# CPU_MISC.net
KiCad netlist of a schematic drawn in Altium Designer
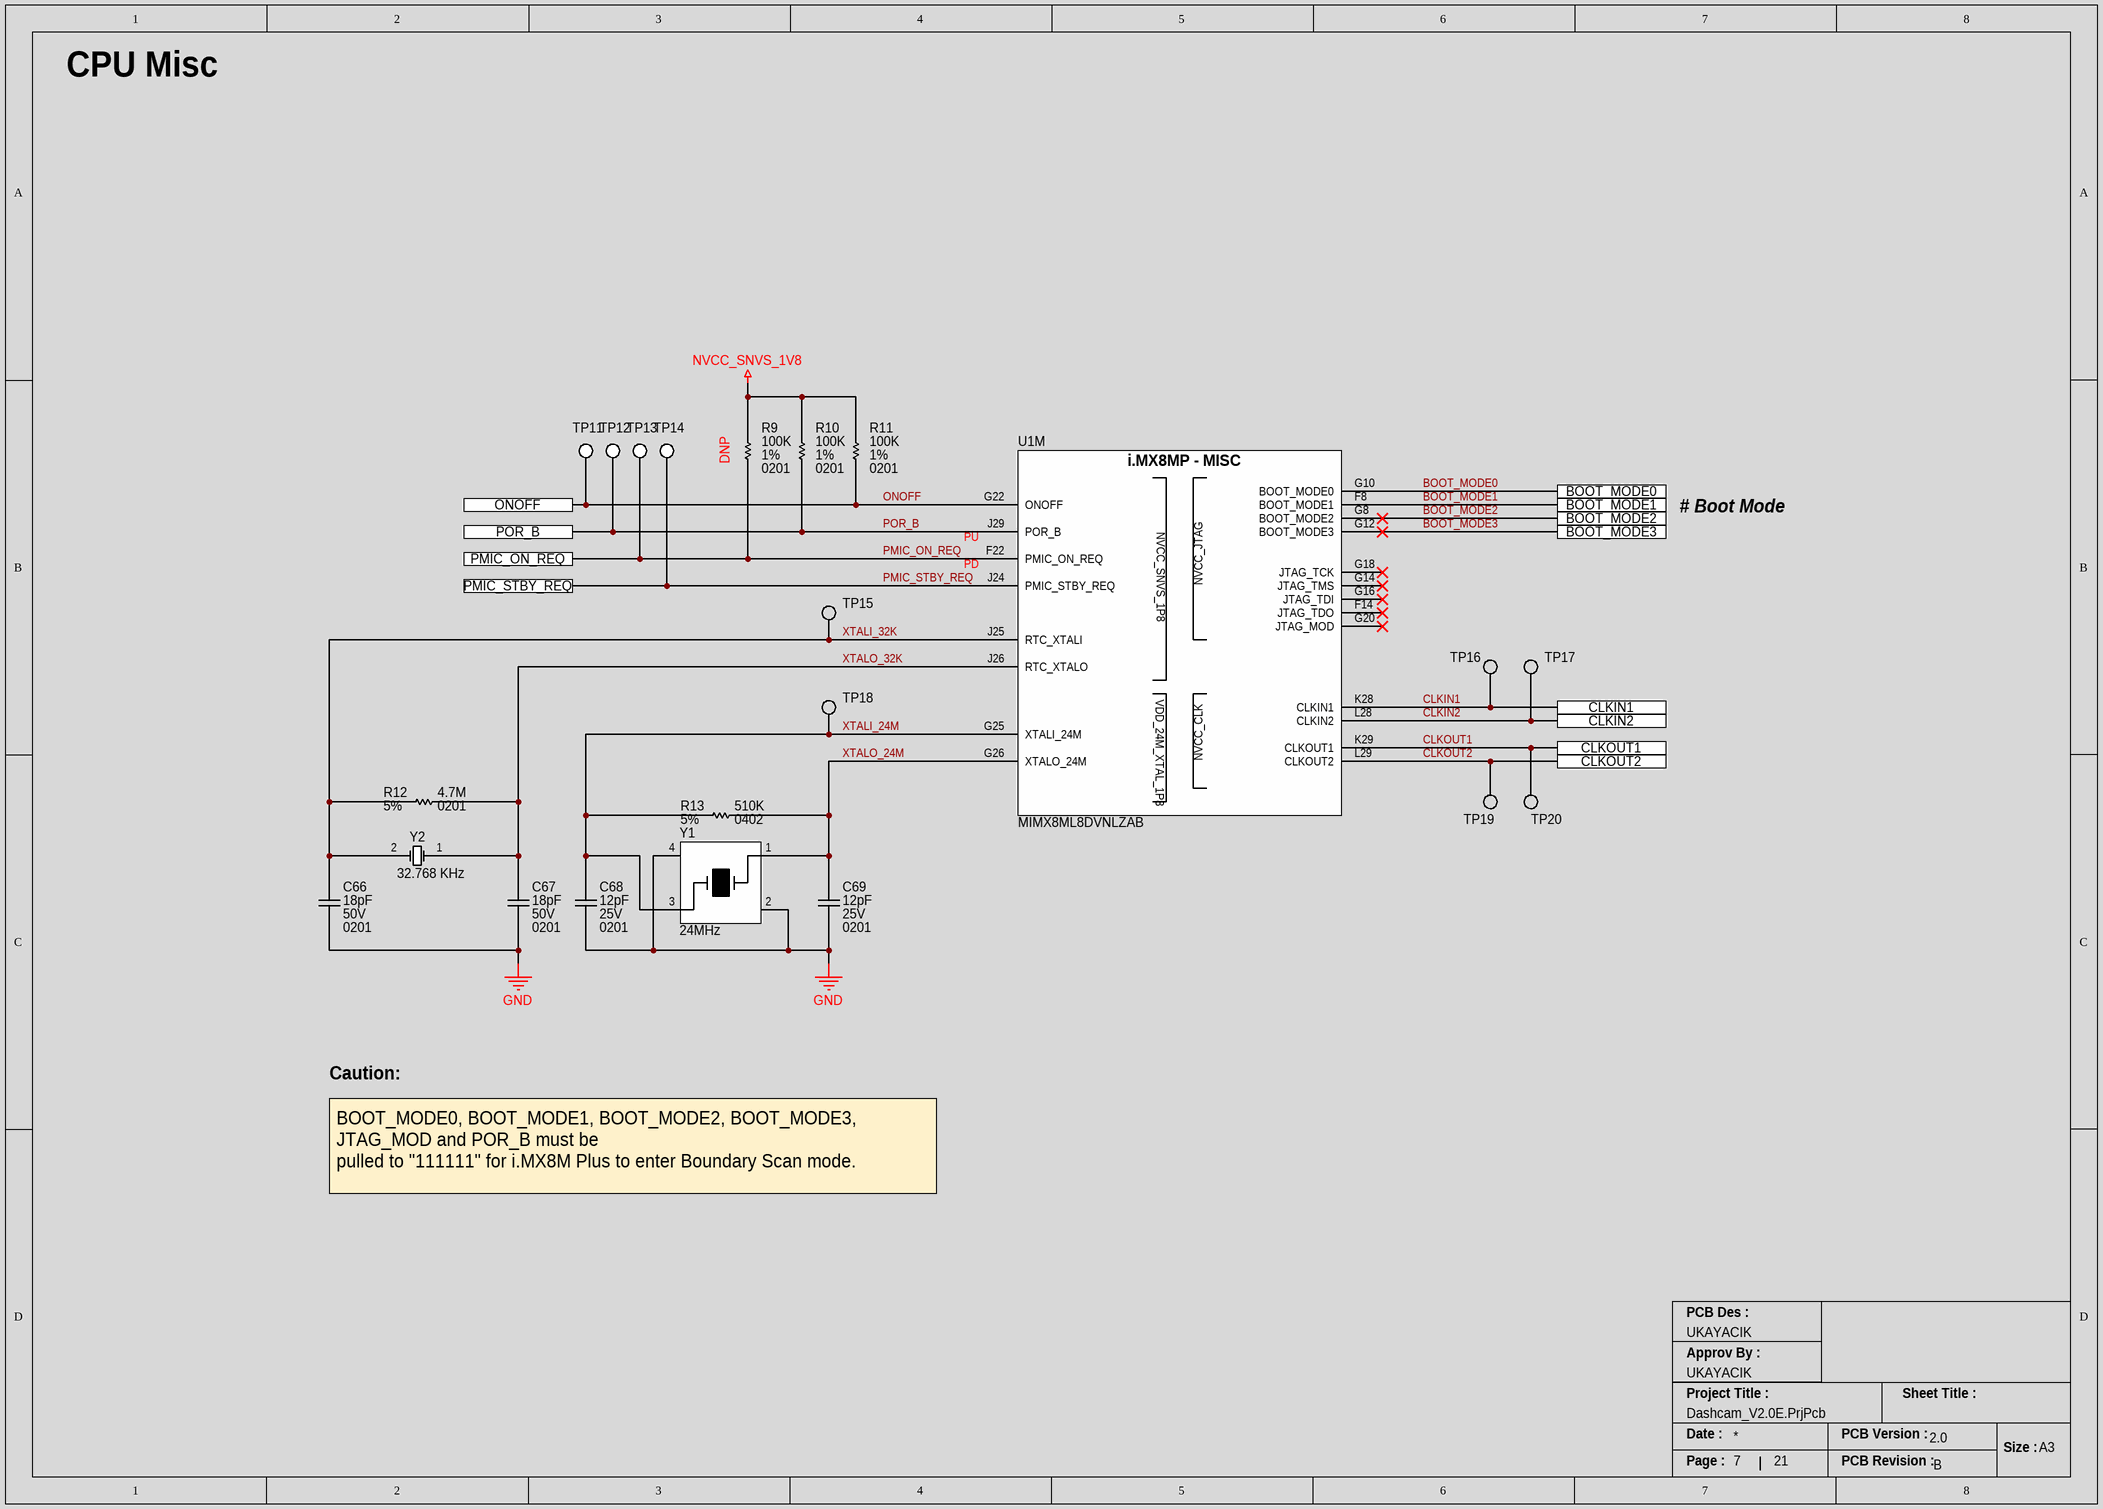
[diagram p0: CPU MISC.SchDoc]

(export (version "E")
  (design (tool "Eeschema 10.0.6"))
  (components
    (comp (ref "C66")
      (value "GRM0335C1H180JA01D")
      (footprint "CAP_0201_CAPC0603X03N")
      (description "Multilayer Ceramic Capacitor, 18 pF, 50 V, ± 5%, C0G (NP0), 0201 [0603 Metric]")
      (fields
        (field (name "MANUFACTURER") "Murata")
        (field (name "TOLERANCE") "5%")
        (field (name "CAPACITANCE") "18pF")
        (field (name "VOLTAGE RATING") "50V")
        (field (name "CASE/PACKAGE") "0201")
      )
      (libsource (lib "Electronic Devices_LIB") (part "CAP_18PF_50V_NP0_0201"))
    )
    (comp (ref "C67")
      (value "GRM0335C1H180JA01D")
      (footprint "CAP_0201_CAPC0603X03N")
      (description "Multilayer Ceramic Capacitor, 18 pF, 50 V, ± 5%, C0G (NP0), 0201 [0603 Metric]")
      (fields
        (field (name "MANUFACTURER") "Murata")
        (field (name "TOLERANCE") "5%")
        (field (name "CAPACITANCE") "18pF")
        (field (name "VOLTAGE RATING") "50V")
        (field (name "CASE/PACKAGE") "0201")
      )
      (libsource (lib "Electronic Devices_LIB") (part "CAP_18PF_50V_NP0_0201"))
    )
    (comp (ref "C68")
      (value "CGA1A2C0G1E120J030BA")
      (footprint "CAP_0201_CAPC0603X03N")
      (description "CAPACITORS CERAMIC, 12PF, 5%, 25V, C0G, 0201[0603]; Product Range: TDK - CGA Seri")
      (fields
        (field (name "MANUFACTURER") "TDK")
        (field (name "TOLERANCE") "5%")
        (field (name "VOLTAGE RATING") "25V")
        (field (name "CAPACITANCE") "12pF")
        (field (name "CASE/PACKAGE") "0201")
      )
      (libsource (lib "Electronic Devices_LIB") (part "CAP_12PF_25V_NP0_0201"))
    )
    (comp (ref "C69")
      (value "CGA1A2C0G1E120J030BA")
      (footprint "CAP_0201_CAPC0603X03N")
      (description "CAPACITORS CERAMIC, 12PF, 5%, 25V, C0G, 0201[0603]; Product Range: TDK - CGA Seri")
      (fields
        (field (name "MANUFACTURER") "TDK")
        (field (name "TOLERANCE") "5%")
        (field (name "VOLTAGE RATING") "25V")
        (field (name "CAPACITANCE") "12pF")
        (field (name "CASE/PACKAGE") "0201")
      )
      (libsource (lib "Electronic Devices_LIB") (part "CAP_12PF_25V_NP0_0201"))
    )
    (comp (ref "R9")
      (value "RC0201FR-07100KL")
      (footprint "RES_0201_RESC0603X02N")
      (description "SMD Chip Resistor, 100 kOhm, ± 1%, 50 mW, 0201 [0603 Metric], Thick Film, General Purpose")
      (fields
        (field (name "MANUFACTURER") "Yageo")
        (field (name "RESISTANCE") "100K")
        (field (name "TOLERANCE") "1%")
        (field (name "CASE/PACKAGE") "0201")
      )
      (libsource (lib "Electronic Devices_LIB") (part "RES_100K_1%_50mW_0201"))
    )
    (comp (ref "R10")
      (value "RC0201FR-07100KL")
      (footprint "RES_0201_RESC0603X02N")
      (description "SMD Chip Resistor, 100 kOhm, ± 1%, 50 mW, 0201 [0603 Metric], Thick Film, General Purpose")
      (fields
        (field (name "MANUFACTURER") "Yageo")
        (field (name "RESISTANCE") "100K")
        (field (name "TOLERANCE") "1%")
        (field (name "CASE/PACKAGE") "0201")
      )
      (libsource (lib "Electronic Devices_LIB") (part "RES_100K_1%_50mW_0201"))
    )
    (comp (ref "R11")
      (value "RC0201FR-07100KL")
      (footprint "RES_0201_RESC0603X02N")
      (description "SMD Chip Resistor, 100 kOhm, ± 1%, 50 mW, 0201 [0603 Metric], Thick Film, General Purpose")
      (fields
        (field (name "MANUFACTURER") "Yageo")
        (field (name "RESISTANCE") "100K")
        (field (name "TOLERANCE") "1%")
        (field (name "CASE/PACKAGE") "0201")
      )
      (libsource (lib "Electronic Devices_LIB") (part "RES_100K_1%_50mW_0201"))
    )
    (comp (ref "R12")
      (value "RC0201JR-074M7L")
      (footprint "RES_0201_RESC0603X02N")
      (description "SMD Chip Resistor, 4.7 MOhm, ± 5%, 50 mW, 0201 [0603 Metric], Thick Film, General Purpose")
      (fields
        (field (name "MANUFACTURER") "Yageo")
        (field (name "TOLERANCE") "5%")
        (field (name "RESISTANCE") "4.7M")
        (field (name "CASE/PACKAGE") "0201")
      )
      (libsource (lib "Electronic Devices_LIB") (part "RES_4.7M_5%_50mW_0201"))
    )
    (comp (ref "R13")
      (value "ERJ-2GEJ514X")
      (footprint "RES_0402_RESC1005X04N")
      (description "SMD Chip Resistor, 510 kOhm, ± 5%, 100 mW, 0402 [1005 Metric], Thick Film, General Purpose")
      (fields
        (field (name "MANUFACTURER") "Panasonic")
        (field (name "TOLERANCE") "5%")
        (field (name "RESISTANCE") "510K")
        (field (name "CASE/PACKAGE") "0402")
      )
      (libsource (lib "Electronic Devices_LIB") (part "RES_510K_5%_100mW_0402"))
    )
    (comp (ref "TP11")
      (value "NO COMPONENT")
      (footprint "TP_PAD_0.8MM_SMD_ROUND")
      (description "Test Point, SMD pad, round, 1.5mm, 1.6mm, 3mm diameter")
      (libsource (lib "Electronic Devices_LIB") (part "TP_PAD_SMD_Round"))
    )
    (comp (ref "TP12")
      (value "NO COMPONENT")
      (footprint "TP_PAD_0.8MM_SMD_ROUND")
      (description "Test Point, SMD pad, round, 1.5mm, 1.6mm, 3mm diameter")
      (libsource (lib "Electronic Devices_LIB") (part "TP_PAD_SMD_Round"))
    )
    (comp (ref "TP13")
      (value "NO COMPONENT")
      (footprint "TP_PAD_0.8MM_SMD_ROUND")
      (description "Test Point, SMD pad, round, 1.5mm, 1.6mm, 3mm diameter")
      (libsource (lib "Electronic Devices_LIB") (part "TP_PAD_SMD_Round"))
    )
    (comp (ref "TP14")
      (value "NO COMPONENT")
      (footprint "TP_PAD_0.8MM_SMD_ROUND")
      (description "Test Point, SMD pad, round, 1.5mm, 1.6mm, 3mm diameter")
      (libsource (lib "Electronic Devices_LIB") (part "TP_PAD_SMD_Round"))
    )
    (comp (ref "TP15")
      (value "NO COMPONENT")
      (footprint "TP_PAD_0.5MM_SMD_ROUND")
      (description "Test Point, SMD pad, round, 1.5mm, 1.6mm, 3mm diameter")
      (libsource (lib "Electronic Devices_LIB") (part "TP_PAD_SMD_SMALL"))
    )
    (comp (ref "TP16")
      (value "NO COMPONENT")
      (footprint "TP_PAD_0.5MM_SMD_ROUND")
      (description "Test Point, SMD pad, round, 1.5mm, 1.6mm, 3mm diameter")
      (libsource (lib "Electronic Devices_LIB") (part "TP_PAD_SMD_SMALL"))
    )
    (comp (ref "TP17")
      (value "NO COMPONENT")
      (footprint "TP_PAD_0.5MM_SMD_ROUND")
      (description "Test Point, SMD pad, round, 1.5mm, 1.6mm, 3mm diameter")
      (libsource (lib "Electronic Devices_LIB") (part "TP_PAD_SMD_SMALL"))
    )
    (comp (ref "TP18")
      (value "NO COMPONENT")
      (footprint "TP_PAD_0.5MM_SMD_ROUND")
      (description "Test Point, SMD pad, round, 1.5mm, 1.6mm, 3mm diameter")
      (libsource (lib "Electronic Devices_LIB") (part "TP_PAD_SMD_SMALL"))
    )
    (comp (ref "TP19")
      (value "NO COMPONENT")
      (footprint "TP_PAD_0.5MM_SMD_ROUND")
      (description "Test Point, SMD pad, round, 1.5mm, 1.6mm, 3mm diameter")
      (libsource (lib "Electronic Devices_LIB") (part "TP_PAD_SMD_SMALL"))
    )
    (comp (ref "TP20")
      (value "NO COMPONENT")
      (footprint "TP_PAD_0.5MM_SMD_ROUND")
      (description "Test Point, SMD pad, round, 1.5mm, 1.6mm, 3mm diameter")
      (libsource (lib "Electronic Devices_LIB") (part "TP_PAD_SMD_SMALL"))
    )
    (comp (ref "U1")
      (value "MIMX8ML8DVNLZAB")
      (footprint "IC_MPU_BGA548C50P29X29_1500X1500X148")
      (description "i.MX 8M Plus, Consumer, / TRAY TRAY MULTIPLE DP BAKEABLE RoHS Compliant: Yes")
      (fields (field (name "MANUFACTURER") "NXP Semiconductors"))
      (libsource (lib "Electronic Devices_LIB") (part "IC_MPU_8M_PLUS_MIMX8ML8DVNLZAB"))
    )
    (comp (ref "Y1")
      (value "TSX-3225 24.0000MF15X-AC3")
      (footprint "CRYSTAL_24MHz_OSCCC320X250X60")
      (description "24 MHz ±10ppm Crystal 9pF 40 Ohms 4-SMD, No Lead")
      (fields (field (name "MANUFACTURER") "Epson") (field (name "FREQUENCY") "24MHz"))
      (libsource (lib "Electronic Devices_LIB") (part "CRYSTAL_EPSON_24MHz_TSX-3225 24.0000MF15X-AC3"))
    )
    (comp (ref "Y2")
      (value "ABS07-32.768KHZ-T")
      (footprint "CRYSTAL_ABS07-32.768KHZ-T")
      (description "Crystal 0.032768MHz ±20ppm (Tol) 12.5pF Flexural 70000Ohm 2-Pin CSMD T/R")
      (fields
        (field (name "MANUFACTURER") "Abracon")
        (field (name "TOLERANCE") "20ppm")
        (field (name "OPERATING FREQUENCY") "32.768 KHz")
      )
      (libsource (lib "Electronic Devices_LIB") (part "CRYSTAL_ABRACON_32.768KHz_ABS07-32.768KHZ-T"))
    )
  )
  (nets
    (net (code "1") (name "/BOOT_MODE0") (class "Default")
      (node (ref "U1") (pin "G10") (pinfunction "BOOT_MODE0_G10") (pintype "passive"))
    )
    (net (code "2") (name "/BOOT_MODE1") (class "Default")
      (node (ref "U1") (pin "F8") (pinfunction "BOOT_MODE1_F8") (pintype "passive"))
    )
    (net (code "3") (name "/BOOT_MODE2") (class "Default")
      (node (ref "U1") (pin "G8") (pinfunction "BOOT_MODE2_G8") (pintype "passive+no_connect"))
    )
    (net (code "4") (name "/BOOT_MODE3") (class "Default")
      (node (ref "U1") (pin "G12") (pinfunction "BOOT_MODE3_G12") (pintype "passive+no_connect"))
    )
    (net (code "5") (name "/CLKIN1") (class "Default")
      (node (ref "TP16") (pin "1") (pinfunction "1_1") (pintype "passive"))
      (node (ref "U1") (pin "K28") (pinfunction "CLKIN1_K28") (pintype "passive"))
    )
    (net (code "6") (name "/CLKIN2") (class "Default")
      (node (ref "TP17") (pin "1") (pinfunction "1_1") (pintype "passive"))
      (node (ref "U1") (pin "L28") (pinfunction "CLKIN2_L28") (pintype "passive"))
    )
    (net (code "7") (name "/CLKOUT1") (class "Default")
      (node (ref "TP20") (pin "1") (pinfunction "1_1") (pintype "passive"))
      (node (ref "U1") (pin "K29") (pinfunction "CLKOUT1_K29") (pintype "passive"))
    )
    (net (code "8") (name "/CLKOUT2") (class "Default")
      (node (ref "TP19") (pin "1") (pinfunction "1_1") (pintype "passive"))
      (node (ref "U1") (pin "L29") (pinfunction "CLKOUT2_L29") (pintype "passive"))
    )
    (net (code "9") (name "/ONOFF") (class "Default")
      (node (ref "R11") (pin "1") (pinfunction "1_1") (pintype "passive"))
      (node (ref "TP11") (pin "1") (pinfunction "1_1") (pintype "passive"))
      (node (ref "U1") (pin "G22") (pinfunction "ONOFF_G22") (pintype "passive"))
    )
    (net (code "10") (name "/PMIC_ON_REQ") (class "Default")
      (node (ref "R9") (pin "1") (pinfunction "1_1") (pintype "passive"))
      (node (ref "TP13") (pin "1") (pinfunction "1_1") (pintype "passive"))
      (node (ref "U1") (pin "F22") (pinfunction "PMIC_ON_REQ_F22") (pintype "passive"))
    )
    (net (code "11") (name "/PMIC_STBY_REQ") (class "Default")
      (node (ref "TP14") (pin "1") (pinfunction "1_1") (pintype "passive"))
      (node (ref "U1") (pin "J24") (pinfunction "PMIC_STBY_REQ_J24") (pintype "passive"))
    )
    (net (code "12") (name "/POR_B") (class "Default")
      (node (ref "R10") (pin "1") (pinfunction "1_1") (pintype "passive"))
      (node (ref "TP12") (pin "1") (pinfunction "1_1") (pintype "passive"))
      (node (ref "U1") (pin "J29") (pinfunction "POR_B_J29") (pintype "passive"))
    )
    (net (code "13") (name "/XTALI_24M") (class "Default")
      (node (ref "C68") (pin "2") (pinfunction "2_2") (pintype "passive"))
      (node (ref "R13") (pin "1") (pinfunction "1_1") (pintype "passive"))
      (node (ref "TP18") (pin "1") (pinfunction "1_1") (pintype "passive"))
      (node (ref "U1") (pin "G25") (pinfunction "XTALI_24M_G25") (pintype "passive"))
      (node (ref "Y1") (pin "3") (pinfunction "3_3") (pintype "passive"))
    )
    (net (code "14") (name "/XTALI_32K") (class "Default")
      (node (ref "C66") (pin "2") (pinfunction "2_2") (pintype "passive"))
      (node (ref "R12") (pin "1") (pinfunction "1_1") (pintype "passive"))
      (node (ref "TP15") (pin "1") (pinfunction "1_1") (pintype "passive"))
      (node (ref "U1") (pin "J25") (pinfunction "RTC_XTALI_J25") (pintype "passive"))
      (node (ref "Y2") (pin "2") (pinfunction "OSC2_2") (pintype "passive"))
    )
    (net (code "15") (name "/XTALO_24M") (class "Default")
      (node (ref "C69") (pin "2") (pinfunction "2_2") (pintype "passive"))
      (node (ref "R13") (pin "2") (pinfunction "2_2") (pintype "passive"))
      (node (ref "U1") (pin "G26") (pinfunction "XTALO_24M_G26") (pintype "passive"))
      (node (ref "Y1") (pin "1") (pinfunction "1_1") (pintype "passive"))
    )
    (net (code "16") (name "/XTALO_32K") (class "Default")
      (node (ref "C67") (pin "2") (pinfunction "2_2") (pintype "passive"))
      (node (ref "R12") (pin "2") (pinfunction "2_2") (pintype "passive"))
      (node (ref "U1") (pin "J26") (pinfunction "RTC_XTALO_J26") (pintype "passive"))
      (node (ref "Y2") (pin "1") (pinfunction "OSC1_1") (pintype "passive"))
    )
    (net (code "17") (name "GND") (class "Default")
      (node (ref "C66") (pin "1") (pinfunction "1_1") (pintype "passive"))
      (node (ref "C67") (pin "1") (pinfunction "1_1") (pintype "passive"))
      (node (ref "C68") (pin "1") (pinfunction "1_1") (pintype "passive"))
      (node (ref "C69") (pin "1") (pinfunction "1_1") (pintype "passive"))
      (node (ref "Y1") (pin "2") (pinfunction "2_2") (pintype "passive"))
      (node (ref "Y1") (pin "4") (pinfunction "4_4") (pintype "passive"))
    )
    (net (code "18") (name "NVCC_SNVS_1V8") (class "Default")
      (node (ref "R10") (pin "2") (pinfunction "2_2") (pintype "passive"))
      (node (ref "R11") (pin "2") (pinfunction "2_2") (pintype "passive"))
      (node (ref "R9") (pin "2") (pinfunction "2_2") (pintype "passive"))
    )
    (net (code "19") (name "unconnected-(U1M-JTAG_MOD-PadG20)") (class "Default")
      (node (ref "U1") (pin "G20") (pinfunction "JTAG_MOD_G20") (pintype "passive+no_connect"))
    )
    (net (code "20") (name "unconnected-(U1M-JTAG_TCK-PadG18)") (class "Default")
      (node (ref "U1") (pin "G18") (pinfunction "JTAG_TCK_G18") (pintype "passive+no_connect"))
    )
    (net (code "21") (name "unconnected-(U1M-JTAG_TDI-PadG16)") (class "Default")
      (node (ref "U1") (pin "G16") (pinfunction "JTAG_TDI_G16") (pintype "passive+no_connect"))
    )
    (net (code "22") (name "unconnected-(U1M-JTAG_TDO-PadF14)") (class "Default")
      (node (ref "U1") (pin "F14") (pinfunction "JTAG_TDO_F14") (pintype "passive+no_connect"))
    )
    (net (code "23") (name "unconnected-(U1M-JTAG_TMS-PadG14)") (class "Default")
      (node (ref "U1") (pin "G14") (pinfunction "JTAG_TMS_G14") (pintype "passive+no_connect"))
    )
  )
)
